# controller.net
KiCad netlist of a schematic drawn in EAGLE
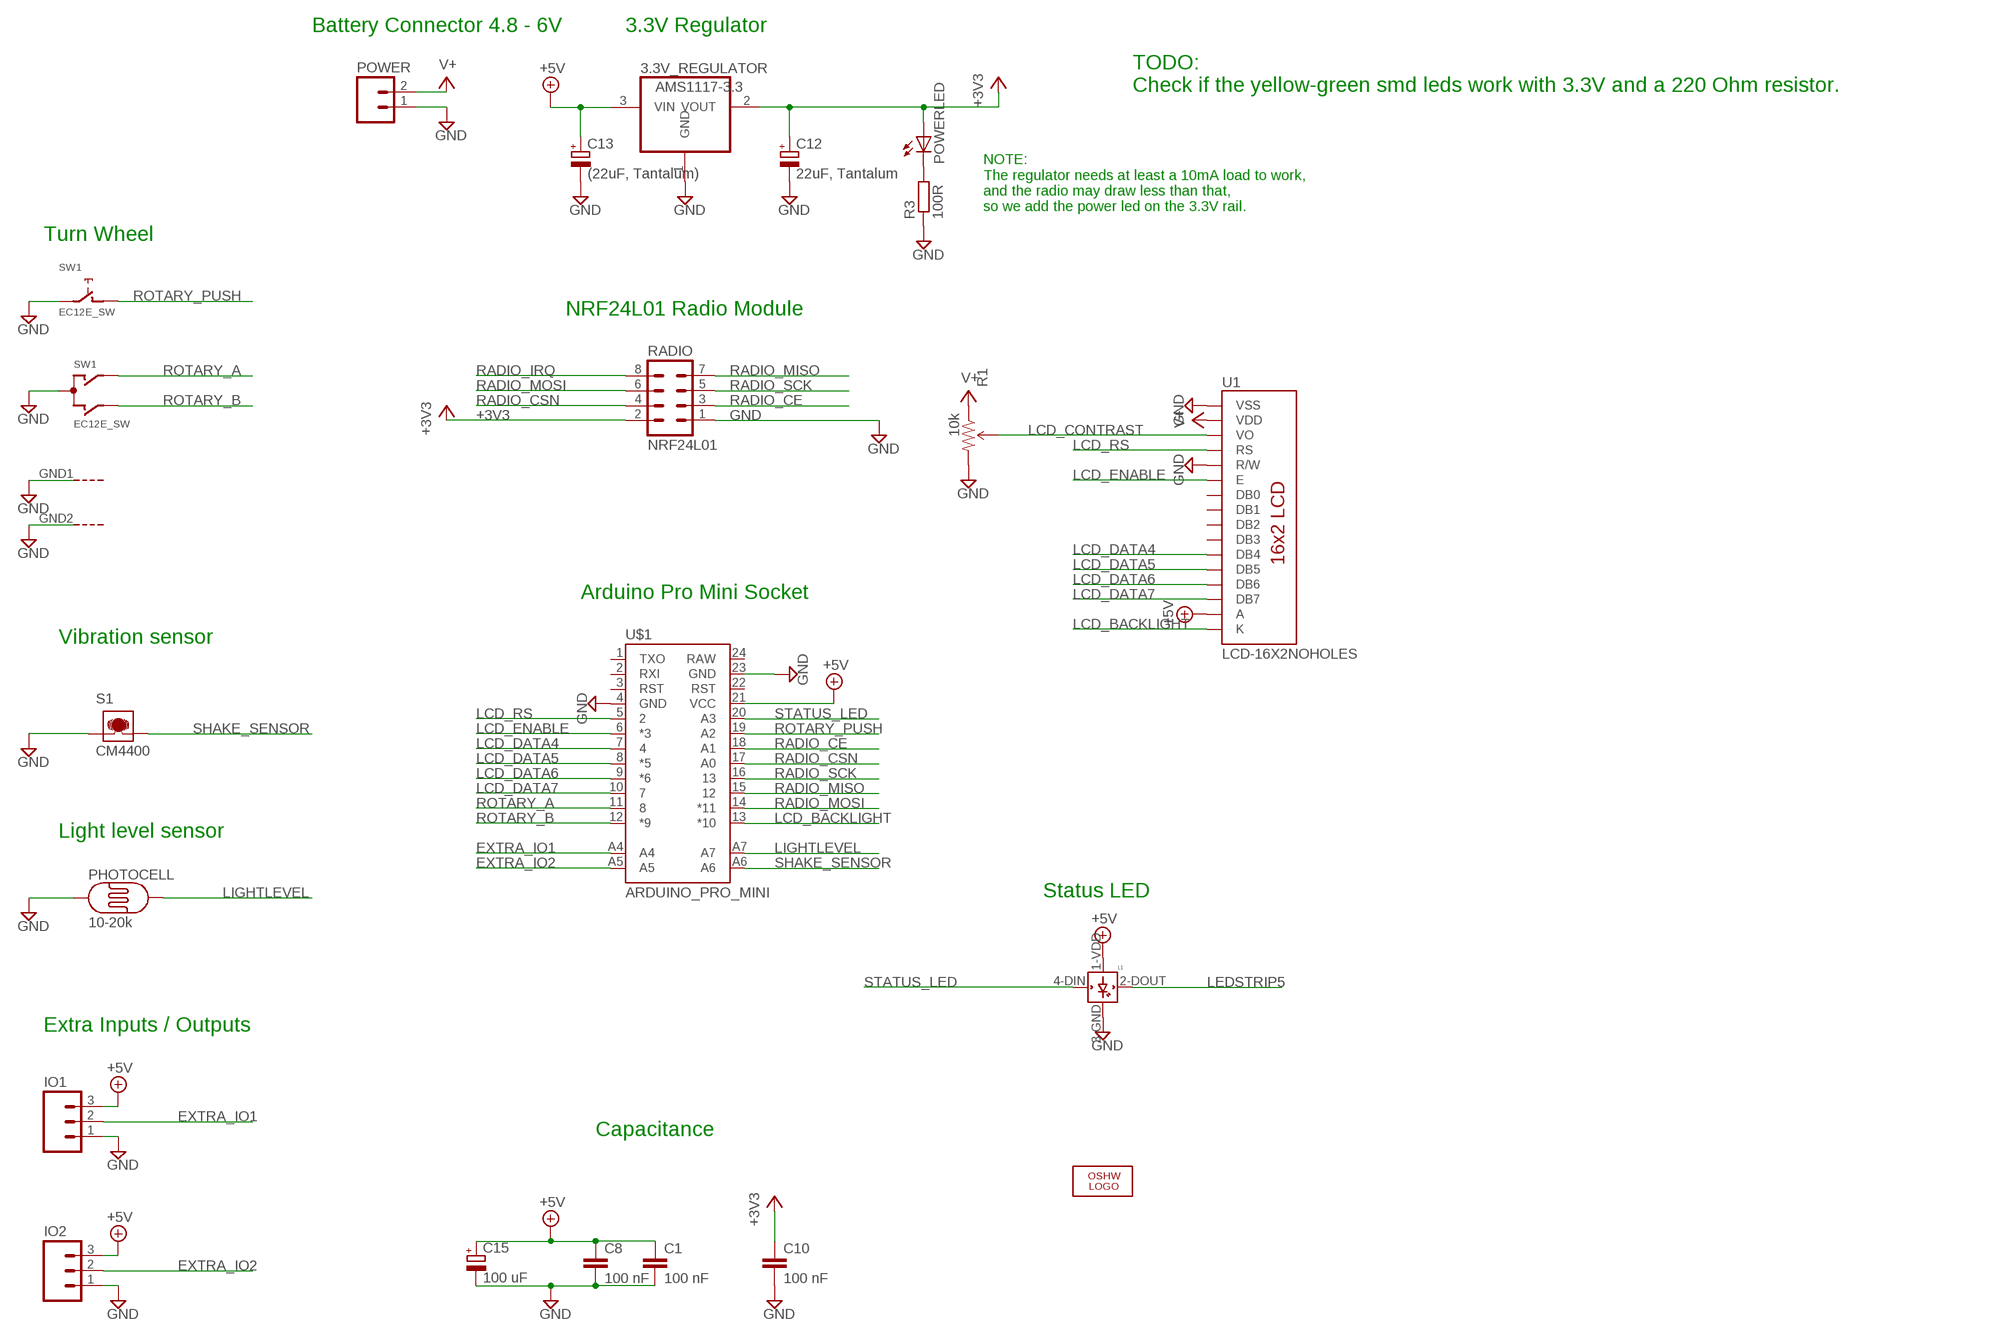
[diagram p0: schematic, sheet 1]

(export (version "E")
  (design (tool "Eeschema 10.0.6"))
  (components
    (comp (ref "3.3V_REGULATOR")
      (value "AMS1117-3.3")
      (footprint "eagle-import:SOT223")
      (fields (field (name "MPN") "REG1117"))
      (libsource (lib "eagle-import") (part "REG1117"))
    )
    (comp (ref "C1")
      (value "100 nF")
      (footprint "eagle-import:C0805")
      (libsource (lib "eagle-import") (part "C-EUC0805"))
    )
    (comp (ref "C8")
      (value "100 nF")
      (footprint "eagle-import:C0805")
      (libsource (lib "eagle-import") (part "C-EUC0805"))
    )
    (comp (ref "C10")
      (value "100 nF")
      (footprint "eagle-import:C0805")
      (libsource (lib "eagle-import") (part "C-EUC0805"))
    )
    (comp (ref "C12")
      (value "22uF, Tantalum")
      (footprint "eagle-import:SMC_A")
      (libsource (lib "eagle-import") (part "CPOL-EUSMCA"))
    )
    (comp (ref "C13")
      (value "(22uF, Tantalum)")
      (footprint "eagle-import:SMC_A")
      (libsource (lib "eagle-import") (part "CPOL-EUSMCA"))
    )
    (comp (ref "C15")
      (value "100 uF")
      (footprint "eagle-import:E2,5-6")
      (libsource (lib "eagle-import") (part "CPOL-EUE2.5-6"))
    )
    (comp (ref "IO1")
      (value "M03PTH")
      (footprint "eagle-import:1X03")
      (libsource (lib "eagle-import") (part "M03PTH"))
    )
    (comp (ref "IO2")
      (value "M03PTH")
      (footprint "eagle-import:1X03")
      (libsource (lib "eagle-import") (part "M03PTH"))
    )
    (comp (ref "L1")
      (value "WS2812B")
      (footprint "eagle-import:WS2812B")
      (libsource (lib "eagle-import") (part "WS2812B"))
    )
    (comp (ref "LOGO3")
      (value "LOGO-OSHW-8MILX0100-NT")
      (footprint "eagle-import:OSHW_8X100_NOTEXT")
      (libsource (lib "eagle-import") (part "LOGO-OSHW-8MILX0100-NT"))
    )
    (comp (ref "PHOTOCELL")
      (value "10-20k")
      (footprint "eagle-import:PHOTOCELL")
      (libsource (lib "eagle-import") (part "PHOTOCELLPTH"))
    )
    (comp (ref "POWER")
      (value "M02LOCK_LONGPADS")
      (footprint "eagle-import:1X02_LOCK_LONGPADS")
      (libsource (lib "eagle-import") (part "M02LOCK_LONGPADS"))
    )
    (comp (ref "POWERLED")
      (value "LEDSMT1206")
      (footprint "eagle-import:1206")
      (libsource (lib "eagle-import") (part "LEDSMT1206"))
    )
    (comp (ref "R1")
      (value "10k")
      (footprint "eagle-import:3362U-2")
      (libsource (lib "eagle-import") (part "TRIMPOT"))
    )
    (comp (ref "R3")
      (value "100R")
      (footprint "eagle-import:M0805")
      (libsource (lib "eagle-import") (part "R-EU_M0805"))
    )
    (comp (ref "RADIO")
      (value "NRF24L01")
      (footprint "eagle-import:MA04-2")
      (libsource (lib "eagle-import") (part "MA04-2"))
    )
    (comp (ref "S1")
      (value "CM4400")
      (footprint "eagle-import:CM4400")
      (fields (field (name "MF") "FARNELL") (field (name "MPN") "CM4400-1."))
      (libsource (lib "eagle-import") (part "CM4400"))
    )
    (comp (ref "SW1")
      (value "EC12E_SW")
      (footprint "eagle-import:ALPS_EC12E_SW")
      (fields (field (name "MPN") "EC12E2424407"))
      (libsource (lib "eagle-import") (part "EC12E_SW"))
    )
    (comp (ref "U$1")
      (value "ARDUINO_PRO_MINI")
      (footprint "eagle-import:ARDUINO_PRO_MINI")
      (libsource (lib "eagle-import") (part "ARDUINO_PRO_MINI"))
    )
    (comp (ref "U1")
      (value "LCD-16X2NOHOLES")
      (footprint "eagle-import:LCD-16X2_NOHOLES")
      (libsource (lib "eagle-import") (part "LCD-16X2NOHOLES"))
    )
  )
  (nets
    (net (code "1") (name "+3V3") (class "Default")
      (node (ref "3.3V_REGULATOR") (pin "2") (pinfunction "VOUT_2") (pintype "output"))
      (node (ref "C10") (pin "1") (pinfunction "1_1") (pintype "passive"))
      (node (ref "C12") (pin "+") (pinfunction "+_+") (pintype "passive"))
      (node (ref "POWERLED") (pin "A") (pinfunction "A_A") (pintype "passive"))
      (node (ref "RADIO") (pin "2") (pinfunction "2_2") (pintype "passive"))
    )
    (net (code "2") (name "+5V") (class "Default")
      (node (ref "3.3V_REGULATOR") (pin "3") (pinfunction "VIN_3") (pintype "input"))
      (node (ref "C1") (pin "1") (pinfunction "1_1") (pintype "passive"))
      (node (ref "C13") (pin "+") (pinfunction "+_+") (pintype "passive"))
      (node (ref "C15") (pin "+") (pinfunction "+_+") (pintype "passive"))
      (node (ref "C8") (pin "1") (pinfunction "1_1") (pintype "passive"))
      (node (ref "IO1") (pin "3") (pinfunction "3_3") (pintype "passive"))
      (node (ref "IO2") (pin "3") (pinfunction "3_3") (pintype "passive"))
      (node (ref "L1") (pin "1-VDD") (pinfunction "VDD_1-VDD") (pintype "bidirectional"))
      (node (ref "U$1") (pin "21") (pinfunction "VCC_21") (pintype "bidirectional"))
      (node (ref "U1") (pin "15") (pinfunction "A_15") (pintype "power_in"))
    )
    (net (code "3") (name "/EXTRA_IO1") (class "Default")
      (node (ref "IO1") (pin "2") (pinfunction "2_2") (pintype "passive"))
      (node (ref "U$1") (pin "A4") (pinfunction "A4_A4") (pintype "bidirectional"))
    )
    (net (code "4") (name "/EXTRA_IO2") (class "Default")
      (node (ref "IO2") (pin "2") (pinfunction "2_2") (pintype "passive"))
      (node (ref "U$1") (pin "A5") (pinfunction "A5_A5") (pintype "bidirectional"))
    )
    (net (code "5") (name "/LCD_BACKLIGHT") (class "Default")
      (node (ref "U$1") (pin "13") (pinfunction "*10_13") (pintype "bidirectional"))
      (node (ref "U1") (pin "16") (pinfunction "K_16") (pintype "power_in"))
    )
    (net (code "6") (name "/LCD_CONTRAST") (class "Default")
      (node (ref "R1") (pin "2") (pinfunction "WIPER_2") (pintype "passive"))
      (node (ref "U1") (pin "3") (pinfunction "VO_3") (pintype "bidirectional"))
    )
    (net (code "7") (name "/LCD_DATA4") (class "Default")
      (node (ref "U$1") (pin "7") (pinfunction "4_7") (pintype "bidirectional"))
      (node (ref "U1") (pin "11") (pinfunction "DB4_11") (pintype "bidirectional"))
    )
    (net (code "8") (name "/LCD_DATA5") (class "Default")
      (node (ref "U$1") (pin "8") (pinfunction "*5_8") (pintype "bidirectional"))
      (node (ref "U1") (pin "12") (pinfunction "DB5_12") (pintype "bidirectional"))
    )
    (net (code "9") (name "/LCD_DATA6") (class "Default")
      (node (ref "U$1") (pin "9") (pinfunction "*6_9") (pintype "bidirectional"))
      (node (ref "U1") (pin "13") (pinfunction "DB6_13") (pintype "bidirectional"))
    )
    (net (code "10") (name "/LCD_DATA7") (class "Default")
      (node (ref "U$1") (pin "10") (pinfunction "7_10") (pintype "bidirectional"))
      (node (ref "U1") (pin "14") (pinfunction "DB7_14") (pintype "bidirectional"))
    )
    (net (code "11") (name "/LCD_ENABLE") (class "Default")
      (node (ref "U$1") (pin "6") (pinfunction "*3_6") (pintype "bidirectional"))
      (node (ref "U1") (pin "6") (pinfunction "E_6") (pintype "input"))
    )
    (net (code "12") (name "/LCD_RS") (class "Default")
      (node (ref "U$1") (pin "5") (pinfunction "2_5") (pintype "bidirectional"))
      (node (ref "U1") (pin "4") (pinfunction "RS_4") (pintype "input"))
    )
    (net (code "13") (name "/LEDSTRIP5") (class "Default")
      (node (ref "L1") (pin "2-DOUT") (pinfunction "DOUT_2-DOUT") (pintype "output"))
    )
    (net (code "14") (name "/LIGHTLEVEL") (class "Default")
      (node (ref "PHOTOCELL") (pin "2") (pinfunction "P$2_2") (pintype "bidirectional"))
      (node (ref "U$1") (pin "A7") (pinfunction "A7_A7") (pintype "bidirectional"))
    )
    (net (code "15") (name "/RADIO_CE") (class "Default")
      (node (ref "RADIO") (pin "3") (pinfunction "3_3") (pintype "passive"))
      (node (ref "U$1") (pin "18") (pinfunction "A1_18") (pintype "bidirectional"))
    )
    (net (code "16") (name "/RADIO_CSN") (class "Default")
      (node (ref "RADIO") (pin "4") (pinfunction "4_4") (pintype "passive"))
      (node (ref "U$1") (pin "17") (pinfunction "A0_17") (pintype "bidirectional"))
    )
    (net (code "17") (name "/RADIO_IRQ") (class "Default")
      (node (ref "RADIO") (pin "8") (pinfunction "8_8") (pintype "passive"))
    )
    (net (code "18") (name "/RADIO_MISO") (class "Default")
      (node (ref "RADIO") (pin "7") (pinfunction "7_7") (pintype "passive"))
      (node (ref "U$1") (pin "15") (pinfunction "12_15") (pintype "bidirectional"))
    )
    (net (code "19") (name "/RADIO_MOSI") (class "Default")
      (node (ref "RADIO") (pin "6") (pinfunction "6_6") (pintype "passive"))
      (node (ref "U$1") (pin "14") (pinfunction "*11_14") (pintype "bidirectional"))
    )
    (net (code "20") (name "/RADIO_SCK") (class "Default")
      (node (ref "RADIO") (pin "5") (pinfunction "5_5") (pintype "passive"))
      (node (ref "U$1") (pin "16") (pinfunction "13_16") (pintype "bidirectional"))
    )
    (net (code "21") (name "/ROTARY_A") (class "Default")
      (node (ref "SW1") (pin "A") (pinfunction "A_A") (pintype "passive"))
      (node (ref "U$1") (pin "11") (pinfunction "8_11") (pintype "bidirectional"))
    )
    (net (code "22") (name "/ROTARY_B") (class "Default")
      (node (ref "SW1") (pin "B") (pinfunction "B_B") (pintype "passive"))
      (node (ref "U$1") (pin "12") (pinfunction "*9_12") (pintype "bidirectional"))
    )
    (net (code "23") (name "/ROTARY_PUSH") (class "Default")
      (node (ref "SW1") (pin "D") (pinfunction "1_D") (pintype "passive"))
      (node (ref "U$1") (pin "19") (pinfunction "A2_19") (pintype "bidirectional"))
    )
    (net (code "24") (name "/SHAKE_SENSOR") (class "Default")
      (node (ref "S1") (pin "2") (pinfunction "2_2") (pintype "passive"))
      (node (ref "U$1") (pin "A6") (pinfunction "A6_A6") (pintype "bidirectional"))
    )
    (net (code "25") (name "/STATUS_LED") (class "Default")
      (node (ref "L1") (pin "4-DIN") (pinfunction "DIN_4-DIN") (pintype "input"))
      (node (ref "U$1") (pin "20") (pinfunction "A3_20") (pintype "bidirectional"))
    )
    (net (code "26") (name "GND") (class "Default")
      (node (ref "3.3V_REGULATOR") (pin "1") (pinfunction "GND_1") (pintype "power_in"))
      (node (ref "C1") (pin "2") (pinfunction "2_2") (pintype "passive"))
      (node (ref "C10") (pin "2") (pinfunction "2_2") (pintype "passive"))
      (node (ref "C12") (pin "-") (pinfunction "-_-") (pintype "passive"))
      (node (ref "C13") (pin "-") (pinfunction "-_-") (pintype "passive"))
      (node (ref "C15") (pin "-") (pinfunction "-_-") (pintype "passive"))
      (node (ref "C8") (pin "2") (pinfunction "2_2") (pintype "passive"))
      (node (ref "IO1") (pin "1") (pinfunction "1_1") (pintype "passive"))
      (node (ref "IO2") (pin "1") (pinfunction "1_1") (pintype "passive"))
      (node (ref "L1") (pin "3-GND") (pinfunction "GND_3-GND") (pintype "bidirectional"))
      (node (ref "PHOTOCELL") (pin "1") (pinfunction "P$1_1") (pintype "bidirectional"))
      (node (ref "POWER") (pin "1") (pinfunction "1_1") (pintype "passive"))
      (node (ref "R1") (pin "3") (pinfunction "CW_3") (pintype "passive"))
      (node (ref "R3") (pin "1") (pinfunction "1_1") (pintype "passive"))
      (node (ref "RADIO") (pin "1") (pinfunction "1_1") (pintype "passive"))
      (node (ref "S1") (pin "1") (pinfunction "1_1") (pintype "passive"))
      (node (ref "SW1") (pin "C") (pinfunction "C_C") (pintype "passive"))
      (node (ref "SW1") (pin "E") (pinfunction "2_E") (pintype "passive"))
      (node (ref "SW1") (pin "GND1") (pinfunction "G_GND1") (pintype "passive"))
      (node (ref "SW1") (pin "GND2") (pinfunction "G_GND2") (pintype "passive"))
      (node (ref "U$1") (pin "23") (pinfunction "GND_23") (pintype "bidirectional"))
      (node (ref "U$1") (pin "4") (pinfunction "GND_4") (pintype "bidirectional"))
      (node (ref "U1") (pin "1") (pinfunction "VSS_1") (pintype "power_in"))
      (node (ref "U1") (pin "5") (pinfunction "R/W_5") (pintype "input"))
    )
    (net (code "27") (name "Net-(POWERLED-PadC)") (class "Default")
      (node (ref "POWERLED") (pin "C") (pinfunction "C_C") (pintype "passive"))
      (node (ref "R3") (pin "2") (pinfunction "2_2") (pintype "passive"))
    )
    (net (code "28") (name "V+") (class "Default")
      (node (ref "POWER") (pin "2") (pinfunction "2_2") (pintype "passive"))
      (node (ref "R1") (pin "1") (pinfunction "CCW_1") (pintype "passive"))
      (node (ref "U1") (pin "2") (pinfunction "VDD_2") (pintype "power_in"))
    )
    (net (code "29") (name "unconnected-(U$1-RAW-Pad24)") (class "Default")
      (node (ref "U$1") (pin "24") (pinfunction "RAW_24") (pintype "bidirectional"))
    )
    (net (code "30") (name "unconnected-(U$1-RST-Pad3)") (class "Default")
      (node (ref "U$1") (pin "3") (pinfunction "RST_3") (pintype "bidirectional"))
    )
    (net (code "31") (name "unconnected-(U$1-RST-Pad22)") (class "Default")
      (node (ref "U$1") (pin "22") (pinfunction "RST_22") (pintype "bidirectional"))
    )
    (net (code "32") (name "unconnected-(U$1-RXI-Pad2)") (class "Default")
      (node (ref "U$1") (pin "2") (pinfunction "RXI_2") (pintype "bidirectional"))
    )
    (net (code "33") (name "unconnected-(U$1-TXO-Pad1)") (class "Default")
      (node (ref "U$1") (pin "1") (pinfunction "TXO_1") (pintype "bidirectional"))
    )
    (net (code "34") (name "unconnected-(U1-DB0-Pad7)") (class "Default")
      (node (ref "U1") (pin "7") (pinfunction "DB0_7") (pintype "bidirectional"))
    )
    (net (code "35") (name "unconnected-(U1-DB1-Pad8)") (class "Default")
      (node (ref "U1") (pin "8") (pinfunction "DB1_8") (pintype "bidirectional"))
    )
    (net (code "36") (name "unconnected-(U1-DB2-Pad9)") (class "Default")
      (node (ref "U1") (pin "9") (pinfunction "DB2_9") (pintype "bidirectional"))
    )
    (net (code "37") (name "unconnected-(U1-DB3-Pad10)") (class "Default")
      (node (ref "U1") (pin "10") (pinfunction "DB3_10") (pintype "bidirectional"))
    )
  )
)
